# POWER.net
KiCad netlist of a schematic drawn in Altium Designer
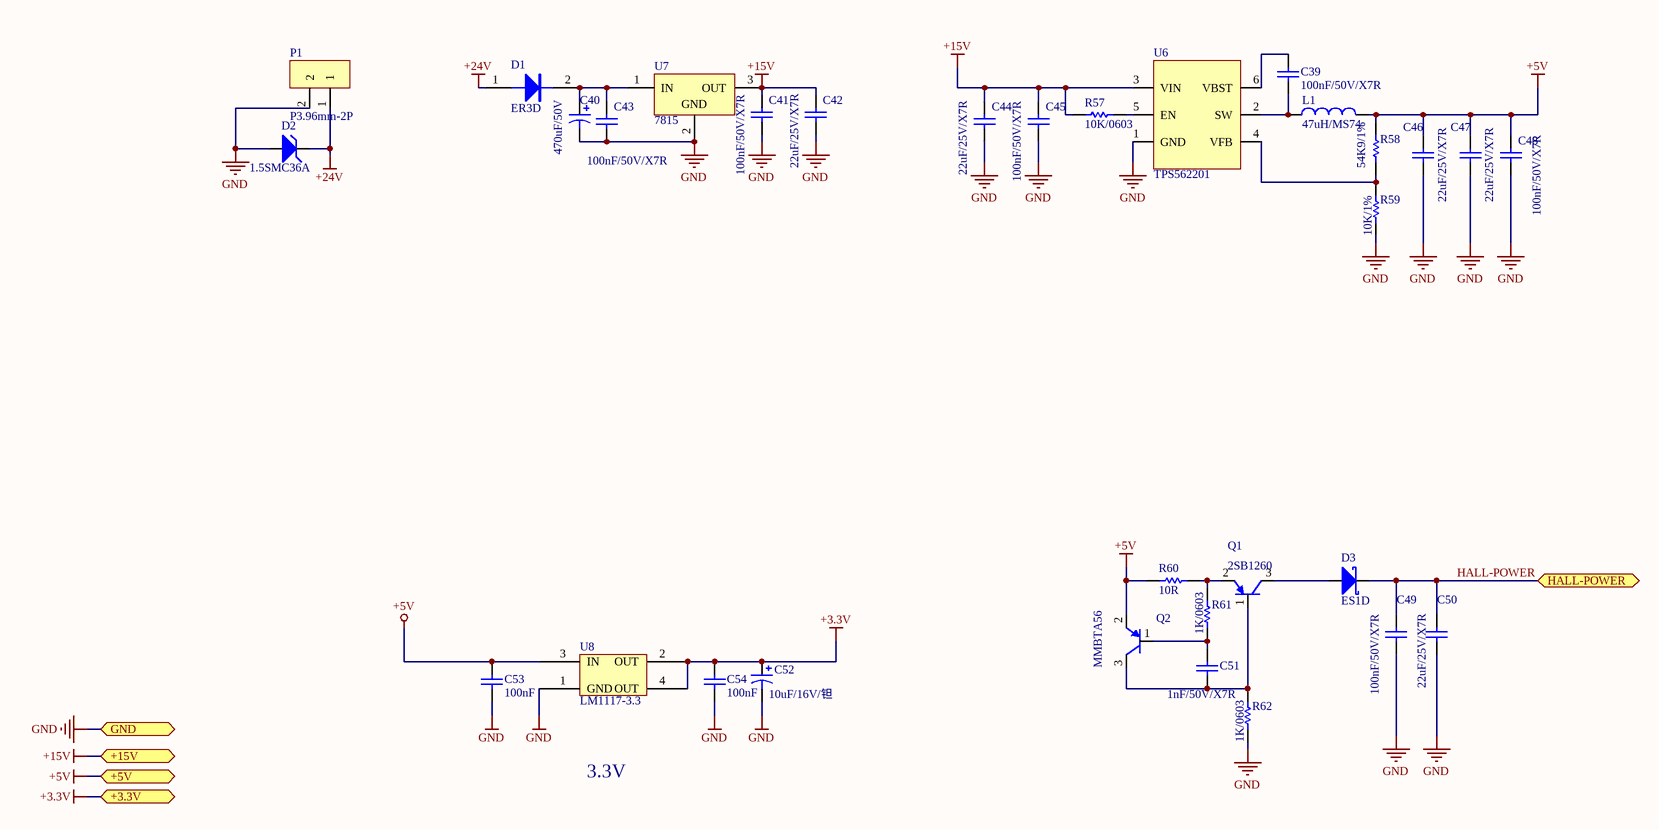
[diagram p0: POWER.SchDoc]

(export (version "E")
  (design (tool "Eeschema 10.0.6"))
  (components
    (comp (ref "C39")
      (value "100nF/50V/X7R")
      (footprint "jichengkuPCB:c0603")
      (libsource (lib "JICHENGKU") (part "Cap"))
    )
    (comp (ref "C40") (value "470uF/50V") (footprint "c10X16") (libsource (lib "JICHENGKU") (part "cap2")))
    (comp (ref "C41")
      (value "100nF/50V/X7R")
      (footprint "jichengkuPCB:c0603")
      (libsource (lib "JICHENGKU") (part "Cap"))
    )
    (comp (ref "C42") (value "22uF/25V/X7R") (footprint "1210") (libsource (lib "JICHENGKU") (part "Cap")))
    (comp (ref "C43")
      (value "100nF/50V/X7R")
      (footprint "jichengkuPCB:c0603")
      (libsource (lib "JICHENGKU") (part "Cap"))
    )
    (comp (ref "C44") (value "22uF/25V/X7R") (footprint "1210") (libsource (lib "JICHENGKU") (part "Cap")))
    (comp (ref "C45")
      (value "100nF/50V/X7R")
      (footprint "jichengkuPCB:c0603")
      (libsource (lib "JICHENGKU") (part "Cap"))
    )
    (comp (ref "C46") (value "22uF/25V/X7R") (footprint "1210") (libsource (lib "JICHENGKU") (part "Cap")))
    (comp (ref "C47") (value "22uF/25V/X7R") (footprint "1210") (libsource (lib "JICHENGKU") (part "Cap")))
    (comp (ref "C48")
      (value "100nF/50V/X7R")
      (footprint "jichengkuPCB:c0603")
      (libsource (lib "JICHENGKU") (part "Cap"))
    )
    (comp (ref "C49")
      (value "100nF/50V/X7R")
      (footprint "jichengkuPCB:c0603")
      (libsource (lib "JICHENGKU") (part "Cap"))
    )
    (comp (ref "C50") (value "22uF/25V/X7R") (footprint "1210") (libsource (lib "JICHENGKU") (part "Cap")))
    (comp (ref "C51")
      (value "1nF/50V/X7R")
      (footprint "jichengkuPCB:c0603")
      (libsource (lib "JICHENGKU") (part "Cap"))
    )
    (comp (ref "C52")
      (value "10uF/16V/钽")
      (footprint "SMD3528-B")
      (libsource (lib "JICHENGKU") (part "cap2"))
    )
    (comp (ref "C53") (value "100nF") (footprint "c0603") (libsource (lib "JICHENGKU") (part "Cap")))
    (comp (ref "C54") (value "100nF") (footprint "c0603") (libsource (lib "JICHENGKU") (part "Cap")))
    (comp (ref "D1")
      (value "ER3D")
      (footprint "jichengkuPCB:SMC")
      (libsource (lib "JICHENGKU") (part "ER3D"))
    )
    (comp (ref "D2")
      (value "1.5SMC36A")
      (footprint "SMC")
      (description "Zener Diode")
      (fields (field (name "PUBLISHER") "Altium Limited"))
      (libsource (lib "*") (part "D Zener"))
    )
    (comp (ref "D3")
      (value "ES1D")
      (footprint "jichengkuPCB:SMA")
      (libsource (lib "JICHENGKU") (part "ES1D"))
    )
    (comp (ref "L1")
      (value "47uH/MS74")
      (footprint "jichengkuPCB:L-7.2*7.2*4")
      (libsource (lib "JICHENGKU") (part "L-7.2*7.2*4"))
    )
    (comp (ref "P1")
      (value "P3.96mm-2P")
      (footprint "P3.96mm-2P")
      (libsource (lib "JICHENGKU") (part "P3.96mm-2P"))
    )
    (comp (ref "Q1")
      (value "2SB1260")
      (footprint "jichengkuPCB:SOT-89")
      (libsource (lib "JICHENGKU") (part "PNP-SOT89"))
    )
    (comp (ref "Q2")
      (value "MMBTA56")
      (footprint "jichengkuPCB:SOT-23")
      (libsource (lib "JICHENGKU") (part "PNP-SOT23"))
    )
    (comp (ref "R57")
      (value "10K/0603")
      (footprint "jichengkuPCB:0603")
      (description "Resistor")
      (libsource (lib "JICHENGKU") (part "R"))
    )
    (comp (ref "R58")
      (value "54K9/1%")
      (footprint "jichengkuPCB:0603")
      (description "Resistor")
      (libsource (lib "JICHENGKU") (part "R"))
    )
    (comp (ref "R59")
      (value "10K/1%")
      (footprint "jichengkuPCB:0603")
      (description "Resistor")
      (libsource (lib "JICHENGKU") (part "R"))
    )
    (comp (ref "R60")
      (value "10R")
      (footprint "0805")
      (description "Resistor")
      (libsource (lib "JICHENGKU") (part "R"))
    )
    (comp (ref "R61")
      (value "1K/0603")
      (footprint "jichengkuPCB:0603")
      (description "Resistor")
      (libsource (lib "JICHENGKU") (part "R"))
    )
    (comp (ref "R62")
      (value "1K/0603")
      (footprint "jichengkuPCB:0603")
      (description "Resistor")
      (libsource (lib "JICHENGKU") (part "R"))
    )
    (comp (ref "U6")
      (value "TPS562201")
      (footprint "jichengkuPCB:SOT-23-6")
      (description "TPS56220x 4.5-V to 17-V Input, 2-A")
      (libsource (lib "JICHENGKU") (part "TPS562201"))
    )
    (comp (ref "U7")
      (value "7815")
      (footprint "D2PAK")
      (description "Micropower Ultra-Low Quiescent Current Voltage Regulator")
      (fields (field (name "PUBLISHER") "Altium Limited"))
      (libsource (lib "ON Semi Power Mgt Voltage Regulator") (part "MC78FC50HT1"))
    )
    (comp (ref "U8")
      (value "LM1117-3.3")
      (footprint "SOT-223")
      (libsource (lib "JICHENGKU") (part "LM1117-3.3"))
    )
  )
  (nets
    (net (code "1") (name "+3.3V") (class "Default")
      (node (ref "C52") (pin "1") (pinfunction "1_1") (pintype "passive"))
      (node (ref "C54") (pin "1") (pinfunction "1_1") (pintype "passive"))
      (node (ref "U8") (pin "2") (pinfunction "OUT_2") (pintype "power_in"))
      (node (ref "U8") (pin "4") (pinfunction "OUT_4") (pintype "power_in"))
    )
    (net (code "2") (name "+5V") (class "Default")
      (node (ref "C46") (pin "2") (pinfunction "2_2") (pintype "passive"))
      (node (ref "C47") (pin "2") (pinfunction "2_2") (pintype "passive"))
      (node (ref "C48") (pin "2") (pinfunction "2_2") (pintype "passive"))
      (node (ref "C53") (pin "1") (pinfunction "1_1") (pintype "passive"))
      (node (ref "L1") (pin "2") (pinfunction "2_2") (pintype "passive"))
      (node (ref "Q2") (pin "2") (pintype "passive"))
      (node (ref "R58") (pin "2") (pinfunction "2_2") (pintype "passive"))
      (node (ref "R60") (pin "1") (pinfunction "1_1") (pintype "passive"))
      (node (ref "U8") (pin "3") (pinfunction "IN_3") (pintype "power_in"))
    )
    (net (code "3") (name "+15V") (class "Default")
      (node (ref "C41") (pin "2") (pinfunction "2_2") (pintype "passive"))
      (node (ref "C42") (pin "2") (pinfunction "2_2") (pintype "passive"))
      (node (ref "C44") (pin "2") (pinfunction "2_2") (pintype "passive"))
      (node (ref "C45") (pin "2") (pinfunction "2_2") (pintype "passive"))
      (node (ref "R57") (pin "1") (pinfunction "1_1") (pintype "passive"))
      (node (ref "U6") (pin "3") (pinfunction "VIN_3") (pintype "passive"))
      (node (ref "U7") (pin "3") (pinfunction "OUT_3") (pintype "power_in"))
    )
    (net (code "4") (name "+24V") (class "Default")
      (node (ref "D1") (pin "1") (pinfunction "A_1") (pintype "passive"))
      (node (ref "D2") (pin "2") (pinfunction "K_2") (pintype "passive"))
      (node (ref "P1") (pin "1") (pinfunction "1_1") (pintype "passive"))
    )
    (net (code "5") (name "/HALL-POWER") (class "Default")
      (node (ref "C49") (pin "2") (pinfunction "2_2") (pintype "passive"))
      (node (ref "C50") (pin "2") (pinfunction "2_2") (pintype "passive"))
      (node (ref "D3") (pin "2") (pinfunction "K_2") (pintype "passive"))
    )
    (net (code "6") (name "GND") (class "Default")
      (node (ref "C40") (pin "2") (pinfunction "2_2") (pintype "passive"))
      (node (ref "C41") (pin "1") (pinfunction "1_1") (pintype "passive"))
      (node (ref "C42") (pin "1") (pinfunction "1_1") (pintype "passive"))
      (node (ref "C43") (pin "1") (pinfunction "1_1") (pintype "passive"))
      (node (ref "C44") (pin "1") (pinfunction "1_1") (pintype "passive"))
      (node (ref "C45") (pin "1") (pinfunction "1_1") (pintype "passive"))
      (node (ref "C46") (pin "1") (pinfunction "1_1") (pintype "passive"))
      (node (ref "C47") (pin "1") (pinfunction "1_1") (pintype "passive"))
      (node (ref "C48") (pin "1") (pinfunction "1_1") (pintype "passive"))
      (node (ref "C49") (pin "1") (pinfunction "1_1") (pintype "passive"))
      (node (ref "C50") (pin "1") (pinfunction "1_1") (pintype "passive"))
      (node (ref "C52") (pin "2") (pinfunction "2_2") (pintype "passive"))
      (node (ref "C53") (pin "2") (pinfunction "2_2") (pintype "passive"))
      (node (ref "C54") (pin "2") (pinfunction "2_2") (pintype "passive"))
      (node (ref "D2") (pin "1") (pinfunction "A_1") (pintype "passive"))
      (node (ref "P1") (pin "2") (pinfunction "2_2") (pintype "passive"))
      (node (ref "R59") (pin "1") (pinfunction "1_1") (pintype "passive"))
      (node (ref "R62") (pin "1") (pinfunction "1_1") (pintype "passive"))
      (node (ref "U6") (pin "1") (pinfunction "GND_1") (pintype "passive"))
      (node (ref "U7") (pin "2") (pinfunction "GND_2") (pintype "power_in"))
      (node (ref "U8") (pin "1") (pinfunction "GND_1") (pintype "power_in"))
    )
    (net (code "7") (name "Net-(C51-Pad1)") (class "Default")
      (node (ref "C51") (pin "1") (pinfunction "1_1") (pintype "passive"))
      (node (ref "Q1") (pin "1") (pintype "passive"))
      (node (ref "Q2") (pin "3") (pintype "passive"))
      (node (ref "R62") (pin "2") (pinfunction "2_2") (pintype "passive"))
    )
    (net (code "8") (name "Net-(C51-Pad2)") (class "Default")
      (node (ref "C51") (pin "2") (pinfunction "2_2") (pintype "passive"))
      (node (ref "Q2") (pin "1") (pintype "passive"))
      (node (ref "R61") (pin "1") (pinfunction "1_1") (pintype "passive"))
    )
    (net (code "9") (name "Net-(D1-K)") (class "Default")
      (node (ref "C40") (pin "1") (pinfunction "1_1") (pintype "passive"))
      (node (ref "C43") (pin "2") (pinfunction "2_2") (pintype "passive"))
      (node (ref "D1") (pin "2") (pinfunction "K_2") (pintype "passive"))
      (node (ref "U7") (pin "1") (pinfunction "IN_1") (pintype "power_in"))
    )
    (net (code "10") (name "Net-(D3-A)") (class "Default")
      (node (ref "D3") (pin "1") (pinfunction "A_1") (pintype "passive"))
      (node (ref "Q1") (pin "3") (pintype "passive"))
    )
    (net (code "11") (name "Net-(Q1-Pad2)") (class "Default")
      (node (ref "Q1") (pin "2") (pintype "passive"))
      (node (ref "R60") (pin "2") (pinfunction "2_2") (pintype "passive"))
      (node (ref "R61") (pin "2") (pinfunction "2_2") (pintype "passive"))
    )
    (net (code "12") (name "Net-(U6-EN)") (class "Default")
      (node (ref "R57") (pin "2") (pinfunction "2_2") (pintype "passive"))
      (node (ref "U6") (pin "5") (pinfunction "EN_5") (pintype "passive"))
    )
    (net (code "13") (name "Net-(U6-SW)") (class "Default")
      (node (ref "C39") (pin "2") (pinfunction "2_2") (pintype "passive"))
      (node (ref "L1") (pin "1") (pinfunction "1_1") (pintype "passive"))
      (node (ref "U6") (pin "2") (pinfunction "SW_2") (pintype "passive"))
    )
    (net (code "14") (name "Net-(U6-VBST)") (class "Default")
      (node (ref "C39") (pin "1") (pinfunction "1_1") (pintype "passive"))
      (node (ref "U6") (pin "6") (pinfunction "VBST_6") (pintype "passive"))
    )
    (net (code "15") (name "Net-(U6-VFB)") (class "Default")
      (node (ref "R58") (pin "1") (pinfunction "1_1") (pintype "passive"))
      (node (ref "R59") (pin "2") (pinfunction "2_2") (pintype "passive"))
      (node (ref "U6") (pin "4") (pinfunction "VFB_4") (pintype "passive"))
    )
  )
)
